# ADC.net
KiCad netlist of a schematic drawn in Altium Designer
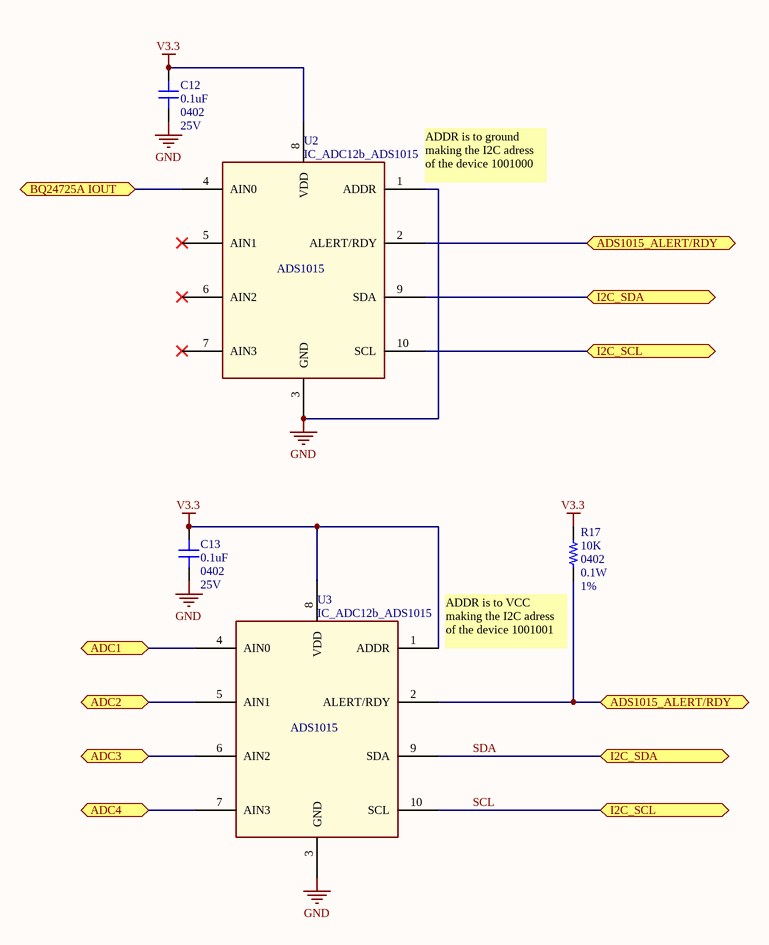
[diagram p0: ADC.SchDoc]

(export (version "E")
  (design (tool "Eeschema 10.0.6"))
  (components
    (comp (ref "C12")
      (value "0.1uF")
      (footprint "CAP_0402")
      (description "CAP CER 0.1uF 25V 0402")
      (fields
        (field (name "PART NUMBER") "CL05A104KA5NNNC‎")
        (field (name "PACKAGE") "0402")
        (field (name "VOLTAGE") "25V")
        (field (name "Comment") "CAP_‎‎CL05A104KA5NNNC‎")
      )
      (libsource (lib "SecureBot") (part "CAP_‎‎CL05A104KA5NNNC‎"))
    )
    (comp (ref "C13")
      (value "0.1uF")
      (footprint "CAP_0402")
      (description "CAP CER 0.1uF 25V 0402")
      (fields
        (field (name "PART NUMBER") "CL05A104KA5NNNC‎")
        (field (name "PACKAGE") "0402")
        (field (name "VOLTAGE") "25V")
        (field (name "Comment") "CAP_‎‎CL05A104KA5NNNC‎")
      )
      (libsource (lib "SecureBot") (part "CAP_‎‎CL05A104KA5NNNC‎"))
    )
    (comp (ref "R17")
      (value "10K")
      (footprint "RES_0402")
      (description "RES 10K 1% 1/10W 0402")
      (fields
        (field (name "PART NUMBER") "‎MCS0402MC1002FE000‎")
        (field (name "PACKAGE") "0402")
        (field (name "POWER") "0.1W")
        (field (name "TOLERANCE") "1%")
        (field (name "Comment") "RES_‎MCS0402MC1002FE000‎")
      )
      (libsource (lib "SecureBot") (part "RES_‎MCS0402MC1002FE000‎"))
    )
    (comp (ref "U2")
      (value "IC_ADC12b_ADS1015")
      (footprint "ADS1015")
      (description "ADC 12-bits with Internal Reference, Oscillator, and Programmable Comparator")
      (fields (field (name "PART NUMBER") "ADS1015"))
      (libsource (lib "SecureBot") (part "IC_ADC12b_ADS1015"))
    )
    (comp (ref "U3")
      (value "IC_ADC12b_ADS1015")
      (footprint "ADS1015")
      (description "ADC 12-bits with Internal Reference, Oscillator, and Programmable Comparator")
      (fields (field (name "PART NUMBER") "ADS1015"))
      (libsource (lib "SecureBot") (part "IC_ADC12b_ADS1015"))
    )
  )
  (nets
    (net (code "1") (name "/ADC1") (class "Default")
      (node (ref "U3") (pin "4") (pinfunction "AIN0_4") (pintype "passive"))
    )
    (net (code "2") (name "/ADC2") (class "Default")
      (node (ref "U3") (pin "5") (pinfunction "AIN1_5") (pintype "passive"))
    )
    (net (code "3") (name "/ADC3") (class "Default")
      (node (ref "U3") (pin "6") (pinfunction "AIN2_6") (pintype "passive"))
    )
    (net (code "4") (name "/ADC4") (class "Default")
      (node (ref "U3") (pin "7") (pinfunction "AIN3_7") (pintype "passive"))
    )
    (net (code "5") (name "/ADS1015_ALERT{slash}RDY") (class "Default")
      (node (ref "R17") (pin "2") (pinfunction "2_2") (pintype "passive"))
      (node (ref "U2") (pin "2") (pinfunction "ALERT/RDY_2") (pintype "passive"))
      (node (ref "U3") (pin "2") (pinfunction "ALERT/RDY_2") (pintype "passive"))
    )
    (net (code "6") (name "/BQ24725A IOUT") (class "Default")
      (node (ref "U2") (pin "4") (pinfunction "AIN0_4") (pintype "passive"))
    )
    (net (code "7") (name "/SCL") (class "Default")
      (node (ref "U2") (pin "10") (pinfunction "SCL_10") (pintype "passive"))
      (node (ref "U3") (pin "10") (pinfunction "SCL_10") (pintype "passive"))
    )
    (net (code "8") (name "/SDA") (class "Default")
      (node (ref "U2") (pin "9") (pinfunction "SDA_9") (pintype "passive"))
      (node (ref "U3") (pin "9") (pinfunction "SDA_9") (pintype "passive"))
    )
    (net (code "9") (name "GND") (class "Default")
      (node (ref "C12") (pin "2") (pinfunction "2_2") (pintype "passive"))
      (node (ref "C13") (pin "2") (pinfunction "2_2") (pintype "passive"))
      (node (ref "U2") (pin "1") (pinfunction "ADDR_1") (pintype "passive"))
      (node (ref "U2") (pin "3") (pinfunction "GND_3") (pintype "passive"))
      (node (ref "U3") (pin "3") (pinfunction "GND_3") (pintype "passive"))
    )
    (net (code "10") (name "V3.3") (class "Default")
      (node (ref "C12") (pin "1") (pinfunction "1_1") (pintype "passive"))
      (node (ref "C13") (pin "1") (pinfunction "1_1") (pintype "passive"))
      (node (ref "R17") (pin "1") (pinfunction "1_1") (pintype "passive"))
      (node (ref "U2") (pin "8") (pinfunction "VDD_8") (pintype "passive"))
      (node (ref "U3") (pin "1") (pinfunction "ADDR_1") (pintype "passive"))
      (node (ref "U3") (pin "8") (pinfunction "VDD_8") (pintype "passive"))
    )
    (net (code "11") (name "unconnected-(U2-AIN1-Pad5)") (class "Default")
      (node (ref "U2") (pin "5") (pinfunction "AIN1_5") (pintype "passive+no_connect"))
    )
    (net (code "12") (name "unconnected-(U2-AIN2-Pad6)") (class "Default")
      (node (ref "U2") (pin "6") (pinfunction "AIN2_6") (pintype "passive+no_connect"))
    )
    (net (code "13") (name "unconnected-(U2-AIN3-Pad7)") (class "Default")
      (node (ref "U2") (pin "7") (pinfunction "AIN3_7") (pintype "passive+no_connect"))
    )
  )
)
